# wm_1.net
KiCad netlist of a schematic drawn in EAGLE
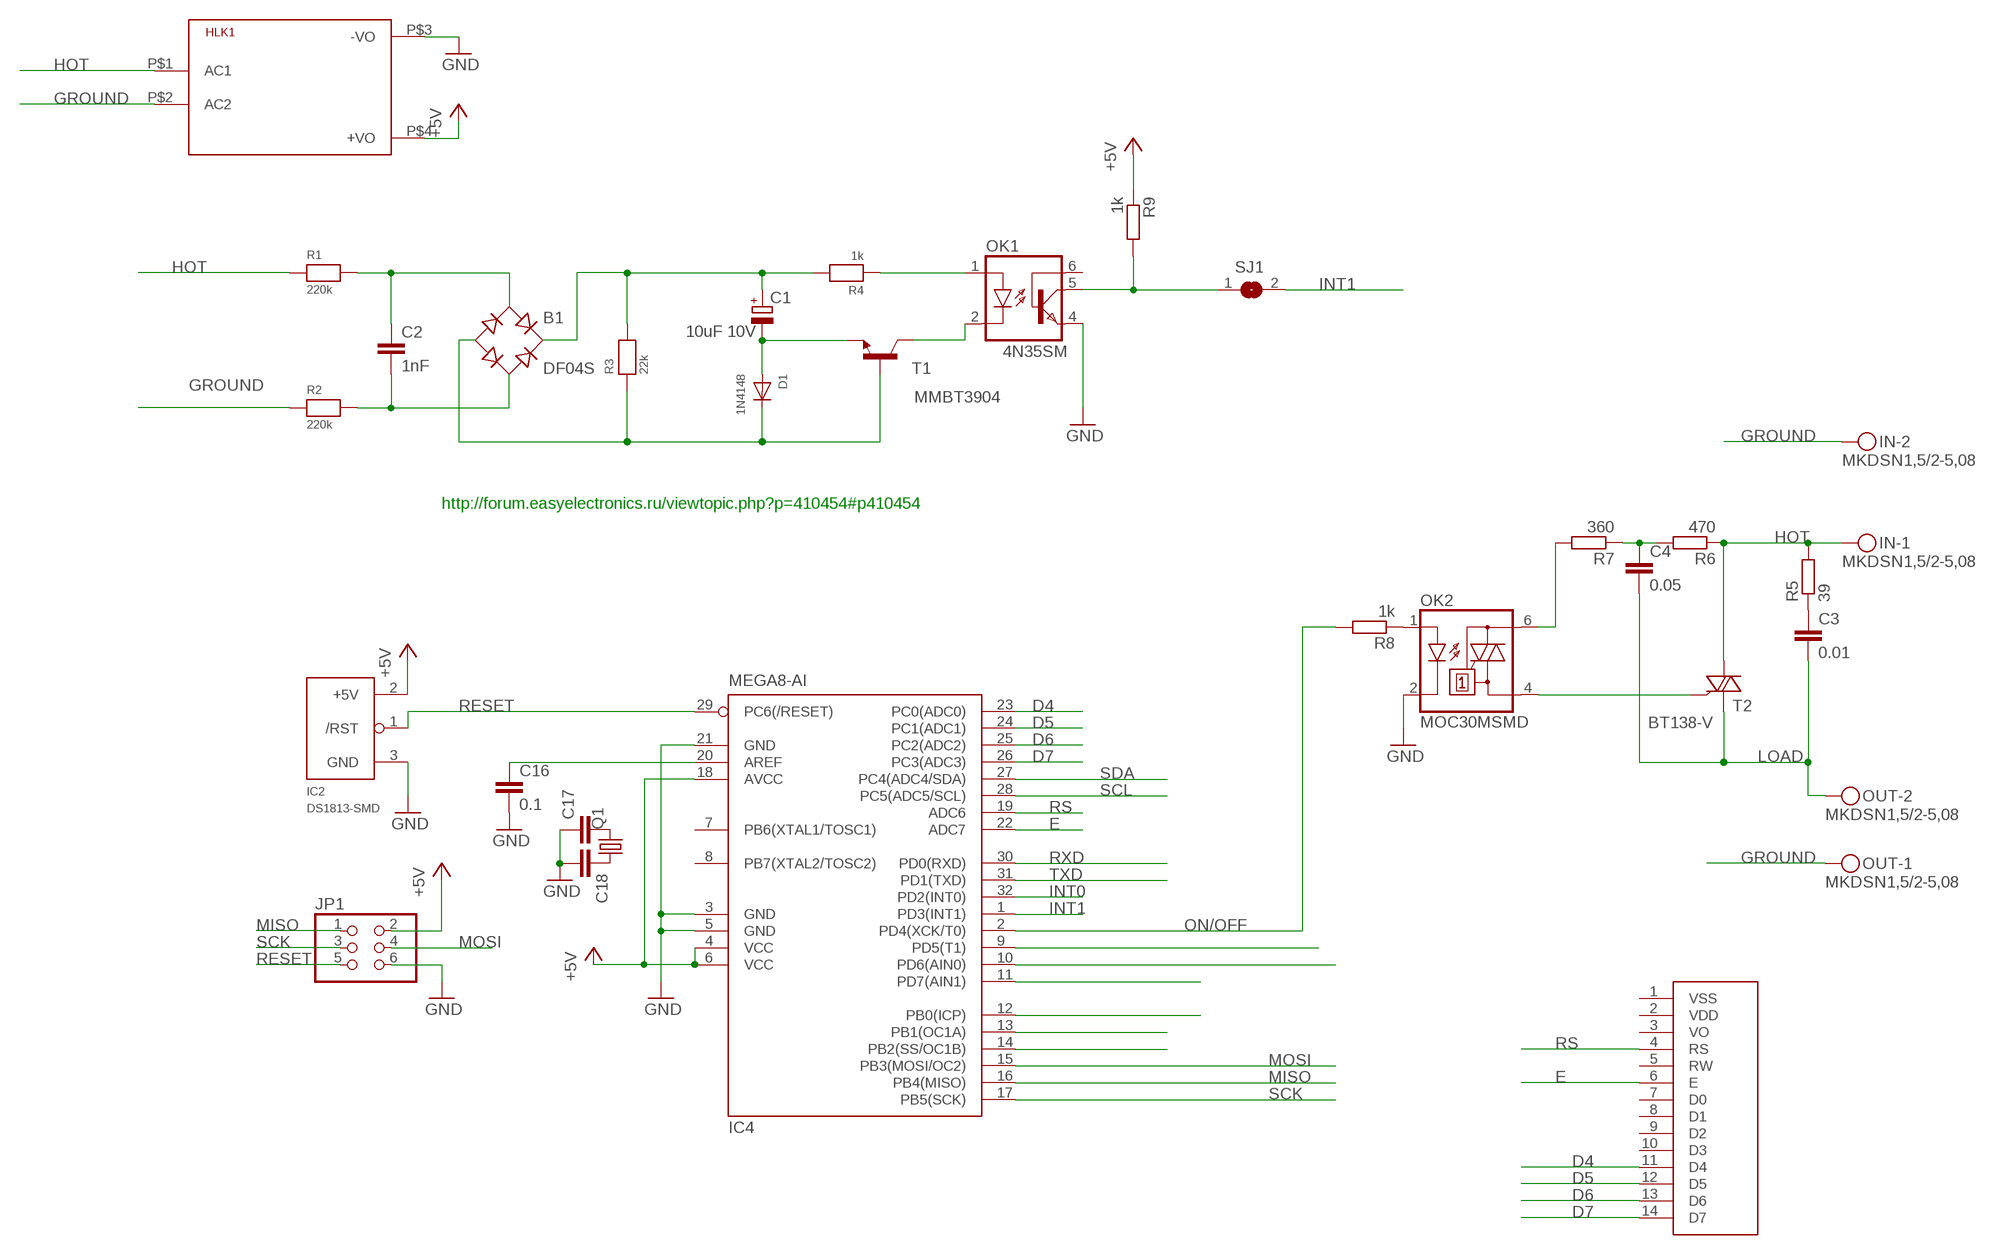
[diagram p0: schematic, sheet 1]

(export (version "E")
  (design (tool "Eeschema 10.0.6"))
  (components
    (comp (ref "B1")
      (value "DF04S")
      (footprint "eagle-import:DFS")
      (libsource (lib "eagle-import") (part "DFS04"))
    )
    (comp (ref "C1")
      (value "10uF 10V")
      (footprint "eagle-import:140CLH-1010")
      (libsource (lib "eagle-import") (part "CPOL-EU140CLH-1010"))
    )
    (comp (ref "C2")
      (value "1nF")
      (footprint "eagle-import:C0805")
      (libsource (lib "eagle-import") (part "rcl_334_C-EUC0805"))
    )
    (comp (ref "C3")
      (value "0.01")
      (footprint "eagle-import:C1206")
      (libsource (lib "eagle-import") (part "rcl_334_C-EUC1206"))
    )
    (comp (ref "C4")
      (value "0.05")
      (footprint "eagle-import:C1206")
      (libsource (lib "eagle-import") (part "rcl_334_C-EUC1206"))
    )
    (comp (ref "C16")
      (value "0.1")
      (footprint "eagle-import:C0805")
      (libsource (lib "eagle-import") (part "C-EUC0805"))
    )
    (comp (ref "C17")
      (value "C-EUC0805")
      (footprint "eagle-import:C0805")
      (libsource (lib "eagle-import") (part "C-EUC0805"))
    )
    (comp (ref "C18")
      (value "C-EUC0805")
      (footprint "eagle-import:C0805")
      (libsource (lib "eagle-import") (part "C-EUC0805"))
    )
    (comp (ref "D1")
      (value "1N4148")
      (footprint "eagle-import:SOD-123")
      (libsource (lib "eagle-import") (part "DIODESOD-123"))
    )
    (comp (ref "HLK1")
      (value "HLK-PM013W")
      (footprint "eagle-import:HLK-PM01")
      (libsource (lib "eagle-import") (part "HLK-PM013W"))
    )
    (comp (ref "IC2")
      (value "DS1813-SMD")
      (footprint "eagle-import:SOT-23")
      (libsource (lib "eagle-import") (part "DS1813-SMD"))
    )
    (comp (ref "IC4")
      (value "MEGA8-AI")
      (footprint "eagle-import:TQFP32-08")
      (fields (field (name "MPN") "ATMEGA8-16AU"))
      (libsource (lib "eagle-import") (part "MEGA8-AI"))
    )
    (comp (ref "IN")
      (value "MKDSN1,5/2-5,08")
      (footprint "eagle-import:MKDSN1,5_2-5,08")
      (libsource (lib "eagle-import") (part "MKDSN1,5/2-5,08"))
    )
    (comp (ref "JP1")
      (value "PINHD-2X3")
      (footprint "eagle-import:2X03")
      (libsource (lib "eagle-import") (part "PINHD-2X3"))
    )
    (comp (ref "OK1")
      (value "4N35SM")
      (footprint "eagle-import:DIL6-SMD")
      (fields (field (name "MF") "FAIRCHILD SEMICONDUCTOR") (field (name "MPN") "4N35S-M"))
      (libsource (lib "eagle-import") (part "4N?MS35"))
    )
    (comp (ref "OK2")
      (value "MOC30MSMD")
      (footprint "eagle-import:DIL6-SMD")
      (libsource (lib "eagle-import") (part "MOC30MSMD"))
    )
    (comp (ref "OUT")
      (value "MKDSN1,5/2-5,08")
      (footprint "eagle-import:MKDSN1,5_2-5,08")
      (libsource (lib "eagle-import") (part "MKDSN1,5/2-5,08"))
    )
    (comp (ref "Q1")
      (value "CRYSTALSM49")
      (footprint "eagle-import:SM49")
      (libsource (lib "eagle-import") (part "CRYSTALSM49"))
    )
    (comp (ref "R1")
      (value "220k")
      (footprint "eagle-import:1206")
      (libsource (lib "eagle-import") (part "RESISTOR1206"))
    )
    (comp (ref "R2")
      (value "220k")
      (footprint "eagle-import:1206")
      (libsource (lib "eagle-import") (part "RESISTOR1206"))
    )
    (comp (ref "R3")
      (value "22k")
      (footprint "eagle-import:1206")
      (libsource (lib "eagle-import") (part "RESISTOR1206"))
    )
    (comp (ref "R4")
      (value "1k")
      (footprint "eagle-import:1206")
      (libsource (lib "eagle-import") (part "RESISTOR1206"))
    )
    (comp (ref "R5")
      (value "39")
      (footprint "eagle-import:R1206")
      (libsource (lib "eagle-import") (part "R-EU_R1206"))
    )
    (comp (ref "R6")
      (value "470")
      (footprint "eagle-import:R1206")
      (libsource (lib "eagle-import") (part "R-EU_R1206"))
    )
    (comp (ref "R7")
      (value "360")
      (footprint "eagle-import:R1206")
      (libsource (lib "eagle-import") (part "R-EU_R1206"))
    )
    (comp (ref "R8")
      (value "1k")
      (footprint "eagle-import:R1206")
      (libsource (lib "eagle-import") (part "R-EU_R1206"))
    )
    (comp (ref "R9")
      (value "1k")
      (footprint "eagle-import:R1206")
      (libsource (lib "eagle-import") (part "R-EU_R1206"))
    )
    (comp (ref "SJ1")
      (value "SOLDERJUMPERREFLOW")
      (footprint "eagle-import:SOLDERJUMPER_REFLOW")
      (libsource (lib "eagle-import") (part "SOLDERJUMPERREFLOW"))
    )
    (comp (ref "T1")
      (value "MMBT3904")
      (footprint "eagle-import:SOT23-BEC")
      (libsource (lib "eagle-import") (part "-NPN-SOT23-BECMMBT3904LT1"))
    )
    (comp (ref "T2")
      (value "BT138-V")
      (footprint "eagle-import:TO220BV")
      (libsource (lib "eagle-import") (part "BT138-V"))
    )
    (comp (ref "U$1")
      (value "2X16LCDSIDE")
      (footprint "eagle-import:2X16LCDSIDE")
      (libsource (lib "eagle-import") (part "2X16LCDSIDE"))
    )
  )
  (nets
    (net (code "1") (name "+5V") (class "Default")
      (node (ref "HLK1") (pin "P$4") (pinfunction "+VO_P$4") (pintype "bidirectional"))
      (node (ref "IC2") (pin "2") (pinfunction "+5V_2") (pintype "power_in"))
      (node (ref "IC4") (pin "18") (pinfunction "AVCC_18") (pintype "power_in"))
      (node (ref "IC4") (pin "4") (pinfunction "VCC_4") (pintype "power_in"))
      (node (ref "IC4") (pin "6") (pinfunction "VCC_6") (pintype "power_in"))
      (node (ref "JP1") (pin "2") (pinfunction "2_2") (pintype "passive"))
      (node (ref "R9") (pin "1") (pinfunction "1_1") (pintype "passive"))
    )
    (net (code "2") (name "/D4") (class "Default")
      (node (ref "IC4") (pin "23") (pinfunction "PC0(ADC0)_23") (pintype "bidirectional"))
      (node (ref "U$1") (pin "11") (pinfunction "D4_11") (pintype "bidirectional"))
    )
    (net (code "3") (name "/D5") (class "Default")
      (node (ref "IC4") (pin "24") (pinfunction "PC1(ADC1)_24") (pintype "bidirectional"))
      (node (ref "U$1") (pin "12") (pinfunction "D5_12") (pintype "bidirectional"))
    )
    (net (code "4") (name "/D6") (class "Default")
      (node (ref "IC4") (pin "25") (pinfunction "PC2(ADC2)_25") (pintype "bidirectional"))
      (node (ref "U$1") (pin "13") (pinfunction "D6_13") (pintype "bidirectional"))
    )
    (net (code "5") (name "/D7") (class "Default")
      (node (ref "IC4") (pin "26") (pinfunction "PC3(ADC3)_26") (pintype "bidirectional"))
      (node (ref "U$1") (pin "14") (pinfunction "D7_14") (pintype "bidirectional"))
    )
    (net (code "6") (name "/E") (class "Default")
      (node (ref "IC4") (pin "22") (pinfunction "ADC7_22") (pintype "bidirectional"))
      (node (ref "U$1") (pin "6") (pinfunction "E_6") (pintype "bidirectional"))
    )
    (net (code "7") (name "/GROUND") (class "Default")
      (node (ref "HLK1") (pin "P$2") (pinfunction "AC2_P$2") (pintype "bidirectional"))
      (node (ref "IN") (pin "2") (pinfunction "KL_2") (pintype "passive"))
      (node (ref "OUT") (pin "1") (pinfunction "KL_1") (pintype "passive"))
      (node (ref "R2") (pin "1") (pinfunction "1_1") (pintype "passive"))
    )
    (net (code "8") (name "/HOT") (class "Default")
      (node (ref "HLK1") (pin "P$1") (pinfunction "AC1_P$1") (pintype "bidirectional"))
      (node (ref "IN") (pin "1") (pinfunction "KL_1") (pintype "passive"))
      (node (ref "R1") (pin "1") (pinfunction "1_1") (pintype "passive"))
      (node (ref "R5") (pin "2") (pinfunction "2_2") (pintype "passive"))
      (node (ref "R6") (pin "1") (pinfunction "1_1") (pintype "passive"))
      (node (ref "T2") (pin "T2") (pinfunction "A2_T2") (pintype "passive"))
    )
    (net (code "9") (name "/INT0") (class "Default")
      (node (ref "IC4") (pin "32") (pinfunction "PD2(INT0)_32") (pintype "bidirectional"))
    )
    (net (code "10") (name "/INT1") (class "Default")
      (node (ref "IC4") (pin "1") (pinfunction "PD3(INT1)_1") (pintype "bidirectional"))
      (node (ref "SJ1") (pin "2") (pinfunction "2_2") (pintype "passive"))
    )
    (net (code "11") (name "/LOAD") (class "Default")
      (node (ref "C3") (pin "2") (pinfunction "2_2") (pintype "passive"))
      (node (ref "C4") (pin "2") (pinfunction "2_2") (pintype "passive"))
      (node (ref "OUT") (pin "2") (pinfunction "KL_2") (pintype "passive"))
      (node (ref "T2") (pin "T1") (pinfunction "A1_T1") (pintype "passive"))
    )
    (net (code "12") (name "/MISO") (class "Default")
      (node (ref "IC4") (pin "16") (pinfunction "PB4(MISO)_16") (pintype "bidirectional"))
      (node (ref "JP1") (pin "1") (pinfunction "1_1") (pintype "passive"))
    )
    (net (code "13") (name "/MOSI") (class "Default")
      (node (ref "IC4") (pin "15") (pinfunction "PB3(MOSI/OC2)_15") (pintype "bidirectional"))
      (node (ref "JP1") (pin "4") (pinfunction "4_4") (pintype "passive"))
    )
    (net (code "14") (name "/ON{slash}OFF") (class "Default")
      (node (ref "IC4") (pin "2") (pinfunction "PD4(XCK/T0)_2") (pintype "bidirectional"))
      (node (ref "R8") (pin "2") (pinfunction "2_2") (pintype "passive"))
    )
    (net (code "15") (name "/RESET") (class "Default")
      (node (ref "IC2") (pin "1") (pinfunction "/RST_1") (pintype "passive"))
      (node (ref "IC4") (pin "29") (pinfunction "PC6(/RESET)_29") (pintype "bidirectional"))
      (node (ref "JP1") (pin "5") (pinfunction "5_5") (pintype "passive"))
    )
    (net (code "16") (name "/RS") (class "Default")
      (node (ref "IC4") (pin "19") (pinfunction "ADC6_19") (pintype "bidirectional"))
      (node (ref "U$1") (pin "4") (pinfunction "RS_4") (pintype "bidirectional"))
    )
    (net (code "17") (name "/RXD") (class "Default")
      (node (ref "IC4") (pin "30") (pinfunction "PD0(RXD)_30") (pintype "bidirectional"))
    )
    (net (code "18") (name "/SCK") (class "Default")
      (node (ref "IC4") (pin "17") (pinfunction "PB5(SCK)_17") (pintype "bidirectional"))
      (node (ref "JP1") (pin "3") (pinfunction "3_3") (pintype "passive"))
    )
    (net (code "19") (name "/SCL") (class "Default")
      (node (ref "IC4") (pin "28") (pinfunction "PC5(ADC5/SCL)_28") (pintype "bidirectional"))
    )
    (net (code "20") (name "/SDA") (class "Default")
      (node (ref "IC4") (pin "27") (pinfunction "PC4(ADC4/SDA)_27") (pintype "bidirectional"))
    )
    (net (code "21") (name "/TXD") (class "Default")
      (node (ref "IC4") (pin "31") (pinfunction "PD1(TXD)_31") (pintype "bidirectional"))
    )
    (net (code "22") (name "GND") (class "Default")
      (node (ref "C16") (pin "2") (pinfunction "2_2") (pintype "passive"))
      (node (ref "C17") (pin "1") (pinfunction "1_1") (pintype "passive"))
      (node (ref "C18") (pin "2") (pinfunction "2_2") (pintype "passive"))
      (node (ref "HLK1") (pin "P$3") (pinfunction "-VO_P$3") (pintype "bidirectional"))
      (node (ref "IC2") (pin "3") (pinfunction "GND_3") (pintype "power_in"))
      (node (ref "IC4") (pin "21") (pinfunction "GND_21") (pintype "power_in"))
      (node (ref "IC4") (pin "3") (pinfunction "GND_3") (pintype "power_in"))
      (node (ref "IC4") (pin "5") (pinfunction "GND_5") (pintype "power_in"))
      (node (ref "JP1") (pin "6") (pinfunction "6_6") (pintype "passive"))
      (node (ref "OK1") (pin "4") (pinfunction "EMI_4") (pintype "passive"))
      (node (ref "OK2") (pin "2") (pinfunction "C_2") (pintype "passive"))
    )
    (net (code "23") (name "Net-(B1-Pad+)") (class "Default")
      (node (ref "B1") (pin "+") (pinfunction "+_+") (pintype "passive"))
      (node (ref "C1") (pin "+") (pinfunction "+_+") (pintype "passive"))
      (node (ref "R3") (pin "2") (pinfunction "2_2") (pintype "passive"))
      (node (ref "R4") (pin "2") (pinfunction "2_2") (pintype "passive"))
    )
    (net (code "24") (name "Net-(B1-Pad-)") (class "Default")
      (node (ref "B1") (pin "-") (pinfunction "-_-") (pintype "passive"))
      (node (ref "D1") (pin "C") (pinfunction "C_C") (pintype "passive"))
      (node (ref "R3") (pin "1") (pinfunction "1_1") (pintype "passive"))
      (node (ref "T1") (pin "B") (pinfunction "B_B") (pintype "passive"))
    )
    (net (code "25") (name "Net-(B1-PadAC1)") (class "Default")
      (node (ref "B1") (pin "AC1") (pinfunction "AC1_AC1") (pintype "passive"))
      (node (ref "C2") (pin "1") (pinfunction "1_1") (pintype "passive"))
      (node (ref "R1") (pin "2") (pinfunction "2_2") (pintype "passive"))
    )
    (net (code "26") (name "Net-(B1-PadAC2)") (class "Default")
      (node (ref "B1") (pin "AC2") (pinfunction "AC2_AC2") (pintype "passive"))
      (node (ref "C2") (pin "2") (pinfunction "2_2") (pintype "passive"))
      (node (ref "R2") (pin "2") (pinfunction "2_2") (pintype "passive"))
    )
    (net (code "27") (name "Net-(C1-Pad-)") (class "Default")
      (node (ref "C1") (pin "-") (pinfunction "-_-") (pintype "passive"))
      (node (ref "D1") (pin "A") (pinfunction "A_A") (pintype "passive"))
      (node (ref "T1") (pin "E") (pinfunction "E_E") (pintype "passive"))
    )
    (net (code "28") (name "Net-(C3-Pad1)") (class "Default")
      (node (ref "C3") (pin "1") (pinfunction "1_1") (pintype "passive"))
      (node (ref "R5") (pin "1") (pinfunction "1_1") (pintype "passive"))
    )
    (net (code "29") (name "Net-(C4-Pad1)") (class "Default")
      (node (ref "C4") (pin "1") (pinfunction "1_1") (pintype "passive"))
      (node (ref "R6") (pin "2") (pinfunction "2_2") (pintype "passive"))
      (node (ref "R7") (pin "1") (pinfunction "1_1") (pintype "passive"))
    )
    (net (code "30") (name "Net-(C17-Pad2)") (class "Default")
      (node (ref "C17") (pin "2") (pinfunction "2_2") (pintype "passive"))
      (node (ref "Q1") (pin "2") (pinfunction "2_2") (pintype "passive"))
    )
    (net (code "31") (name "Net-(C18-Pad1)") (class "Default")
      (node (ref "C18") (pin "1") (pinfunction "1_1") (pintype "passive"))
      (node (ref "Q1") (pin "1") (pinfunction "1_1") (pintype "passive"))
    )
    (net (code "32") (name "Net-(IC4-AREF)") (class "Default")
      (node (ref "C16") (pin "1") (pinfunction "1_1") (pintype "passive"))
      (node (ref "IC4") (pin "20") (pinfunction "AREF_20") (pintype "passive"))
    )
    (net (code "33") (name "Net-(OK1-A)") (class "Default")
      (node (ref "OK1") (pin "1") (pinfunction "A_1") (pintype "passive"))
      (node (ref "R4") (pin "1") (pinfunction "1_1") (pintype "passive"))
    )
    (net (code "34") (name "Net-(OK1-C)") (class "Default")
      (node (ref "OK1") (pin "2") (pinfunction "C_2") (pintype "passive"))
      (node (ref "T1") (pin "C") (pinfunction "C_C") (pintype "passive"))
    )
    (net (code "35") (name "Net-(OK1-COL)") (class "Default")
      (node (ref "OK1") (pin "5") (pinfunction "COL_5") (pintype "passive"))
      (node (ref "R9") (pin "2") (pinfunction "2_2") (pintype "passive"))
      (node (ref "SJ1") (pin "1") (pinfunction "1_1") (pintype "passive"))
    )
    (net (code "36") (name "Net-(OK2-A)") (class "Default")
      (node (ref "OK2") (pin "1") (pinfunction "A_1") (pintype "passive"))
      (node (ref "R8") (pin "1") (pinfunction "1_1") (pintype "passive"))
    )
    (net (code "37") (name "Net-(OK2-A1)") (class "Default")
      (node (ref "OK2") (pin "4") (pinfunction "A1_4") (pintype "passive"))
      (node (ref "T2") (pin "G") (pinfunction "G_G") (pintype "passive"))
    )
    (net (code "38") (name "Net-(OK2-A2)") (class "Default")
      (node (ref "OK2") (pin "6") (pinfunction "A2_6") (pintype "passive"))
      (node (ref "R7") (pin "2") (pinfunction "2_2") (pintype "passive"))
    )
    (net (code "39") (name "unconnected-(IC4-PB0(ICP)-Pad12)") (class "Default")
      (node (ref "IC4") (pin "12") (pinfunction "PB0(ICP)_12") (pintype "bidirectional"))
    )
    (net (code "40") (name "unconnected-(IC4-PB1(OC1A)-Pad13)") (class "Default")
      (node (ref "IC4") (pin "13") (pinfunction "PB1(OC1A)_13") (pintype "bidirectional"))
    )
    (net (code "41") (name "unconnected-(IC4-PB2(SS{slash}OC1B)-Pad14)") (class "Default")
      (node (ref "IC4") (pin "14") (pinfunction "PB2(SS/OC1B)_14") (pintype "bidirectional"))
    )
    (net (code "42") (name "unconnected-(IC4-PB6(XTAL1{slash}TOSC1)-Pad7)") (class "Default")
      (node (ref "IC4") (pin "7") (pinfunction "PB6(XTAL1/TOSC1)_7") (pintype "bidirectional"))
    )
    (net (code "43") (name "unconnected-(IC4-PB7(XTAL2{slash}TOSC2)-Pad8)") (class "Default")
      (node (ref "IC4") (pin "8") (pinfunction "PB7(XTAL2/TOSC2)_8") (pintype "bidirectional"))
    )
    (net (code "44") (name "unconnected-(IC4-PD5(T1)-Pad9)") (class "Default")
      (node (ref "IC4") (pin "9") (pinfunction "PD5(T1)_9") (pintype "bidirectional"))
    )
    (net (code "45") (name "unconnected-(IC4-PD6(AIN0)-Pad10)") (class "Default")
      (node (ref "IC4") (pin "10") (pinfunction "PD6(AIN0)_10") (pintype "bidirectional"))
    )
    (net (code "46") (name "unconnected-(IC4-PD7(AIN1)-Pad11)") (class "Default")
      (node (ref "IC4") (pin "11") (pinfunction "PD7(AIN1)_11") (pintype "bidirectional"))
    )
    (net (code "47") (name "unconnected-(OK1-BAS-Pad6)") (class "Default")
      (node (ref "OK1") (pin "6") (pinfunction "BAS_6") (pintype "passive"))
    )
    (net (code "48") (name "unconnected-(U$1-D0-Pad7)") (class "Default")
      (node (ref "U$1") (pin "7") (pinfunction "D0_7") (pintype "bidirectional"))
    )
    (net (code "49") (name "unconnected-(U$1-D1-Pad8)") (class "Default")
      (node (ref "U$1") (pin "8") (pinfunction "D1_8") (pintype "bidirectional"))
    )
    (net (code "50") (name "unconnected-(U$1-D2-Pad9)") (class "Default")
      (node (ref "U$1") (pin "9") (pinfunction "D2_9") (pintype "bidirectional"))
    )
    (net (code "51") (name "unconnected-(U$1-D3-Pad10)") (class "Default")
      (node (ref "U$1") (pin "10") (pinfunction "D3_10") (pintype "bidirectional"))
    )
    (net (code "52") (name "unconnected-(U$1-RW-Pad5)") (class "Default")
      (node (ref "U$1") (pin "5") (pinfunction "RW_5") (pintype "bidirectional"))
    )
    (net (code "53") (name "unconnected-(U$1-VDD-Pad2)") (class "Default")
      (node (ref "U$1") (pin "2") (pinfunction "VDD_2") (pintype "bidirectional"))
    )
    (net (code "54") (name "unconnected-(U$1-VO-Pad3)") (class "Default")
      (node (ref "U$1") (pin "3") (pinfunction "VO_3") (pintype "bidirectional"))
    )
    (net (code "55") (name "unconnected-(U$1-VSS-Pad1)") (class "Default")
      (node (ref "U$1") (pin "1") (pinfunction "VSS_1") (pintype "bidirectional"))
    )
  )
)
